# 3v3_LDO.net
KiCad netlist of a schematic drawn in Altium Designer
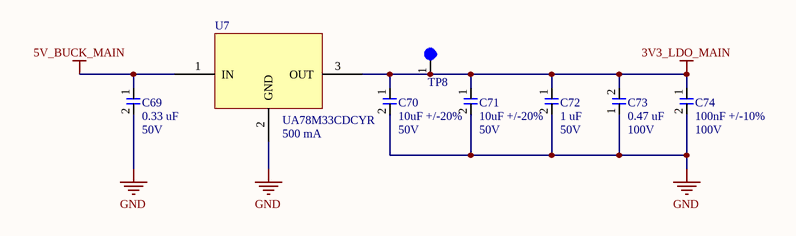
[diagram p0: 3v3_LDO.SchDoc]

(export (version "E")
  (design (tool "Eeschema 10.0.6"))
  (components
    (comp (ref "C69")
      (value "CGA3E3X7R1H334K080AB")
      (footprint "CAP-0603")
      (description "0.33 µF ±10% 50V Ceramic Capacitor X7R 0603 (1608 Metric)")
      (fields
        (field (name "MANUFACTURER") "TDK Corporation")
        (field (name "TOLERANCE") "+/- 10%")
        (field (name "CAPACITANCE") "0.33 uF")
        (field (name "VOLTAGE") "50V")
      )
      (libsource (lib "MasterLib") (part "CAP-0.33uF-0001"))
    )
    (comp (ref "C70")
      (value "CL31B106KBHNNNE")
      (footprint "CAP-1206")
      (description "10 µF ±10% 50V Ceramic Capacitor X7R 1206 (3216 Metric)")
      (fields
        (field (name "MANUFACTURER") "Samsung Electro-Mechanics")
        (field (name "CAPACITANCE") "10uF +/-20%")
        (field (name "VOLTAGE RATING") "50V")
      )
      (libsource (lib "MasterLib") (part "CAP-10U-0001"))
    )
    (comp (ref "C71")
      (value "CL31B106KBHNNNE")
      (footprint "CAP-1206")
      (description "10 µF ±10% 50V Ceramic Capacitor X7R 1206 (3216 Metric)")
      (fields
        (field (name "MANUFACTURER") "Samsung Electro-Mechanics")
        (field (name "CAPACITANCE") "10uF +/-20%")
        (field (name "VOLTAGE RATING") "50V")
      )
      (libsource (lib "MasterLib") (part "CAP-10U-0001"))
    )
    (comp (ref "C72")
      (value "UMK107AB7105KA-T")
      (footprint "CAP-0603")
      (description "1 µF ±10% 50V Ceramic Capacitor X7R 0603 (1608 Metric)")
      (fields (field (name "CAPACITANCE") "1 uF") (field (name "VOLTAGE") "50V"))
      (libsource (lib "MasterLib") (part "CAP-1U-0002"))
    )
    (comp (ref "C73")
      (value "KAM21KR72A474KL")
      (footprint "CAP-0805")
      (description "0.47 µF ±10% 100V Ceramic Capacitor X7R 0805 (2012 Metric)")
      (fields
        (field (name "TOLERANCE") "+/- 10%")
        (field (name "CAPACITANCE") "0.47 uF")
        (field (name "VOLTAGE") "100V")
      )
      (libsource (lib "MasterLib") (part "CAP-0.47U-0001"))
    )
    (comp (ref "C74")
      (value "CC0603KRX7R0BB104")
      (footprint "CAP-0603")
      (description "CAP CER 0.1UF 100V X7R 0603")
      (fields
        (field (name "MANUFACTURER") "YAGEO")
        (field (name "CAPACITANCE") "100nF +/-10%")
        (field (name "VOLTAGE RATING") "100V")
      )
      (libsource (lib "MasterLib") (part "CAP-100N-0001"))
    )
    (comp (ref "TP8")
      (value "5003")
      (footprint "TEST-POINT-0001")
      (description "Oranange PC Test Point, Miniature Phoisphor Bronze Silver Plating Through Hole Mounting Type")
      (libsource (lib "MasterLib") (part "TEST-POINT-0001"))
    )
    (comp (ref "U7")
      (value "UA78M33CDCYR")
      (footprint "IC-SOT-223-4")
      (description "Linear Voltage Regulator IC Positive Fixed 1 Output 500mA SOT-223-4")
      (fields (field (name "CURRENT") "500 mA"))
      (libsource (lib "MasterLib") (part "IC-LDO-3.3V-0002"))
    )
  )
  (nets
    (net (code "1") (name "3V3_LDO_MAIN") (class "Default")
      (node (ref "C70") (pin "1") (pinfunction "1_1") (pintype "passive"))
      (node (ref "C71") (pin "1") (pinfunction "1_1") (pintype "passive"))
      (node (ref "C72") (pin "1") (pinfunction "1_1") (pintype "passive"))
      (node (ref "C73") (pin "2") (pinfunction "2_2") (pintype "passive"))
      (node (ref "C74") (pin "1") (pinfunction "1_1") (pintype "passive"))
      (node (ref "TP8") (pin "1") (pinfunction "0_1") (pintype "passive"))
      (node (ref "U7") (pin "3") (pinfunction "OUT_3") (pintype "power_in"))
    )
    (net (code "2") (name "5V_BUCK_MAIN") (class "Default")
      (node (ref "C69") (pin "1") (pinfunction "1_1") (pintype "passive"))
      (node (ref "U7") (pin "1") (pinfunction "IN_1") (pintype "power_in"))
    )
    (net (code "3") (name "GND") (class "Default")
      (node (ref "C69") (pin "2") (pinfunction "2_2") (pintype "passive"))
      (node (ref "C70") (pin "2") (pinfunction "2_2") (pintype "passive"))
      (node (ref "C71") (pin "2") (pinfunction "2_2") (pintype "passive"))
      (node (ref "C72") (pin "2") (pinfunction "2_2") (pintype "passive"))
      (node (ref "C73") (pin "1") (pinfunction "1_1") (pintype "passive"))
      (node (ref "C74") (pin "2") (pinfunction "2_2") (pintype "passive"))
      (node (ref "U7") (pin "2") (pinfunction "GND_2") (pintype "power_in"))
    )
  )
)
